# SCH1_Main.net
KiCad netlist of a schematic drawn in Altium Designer
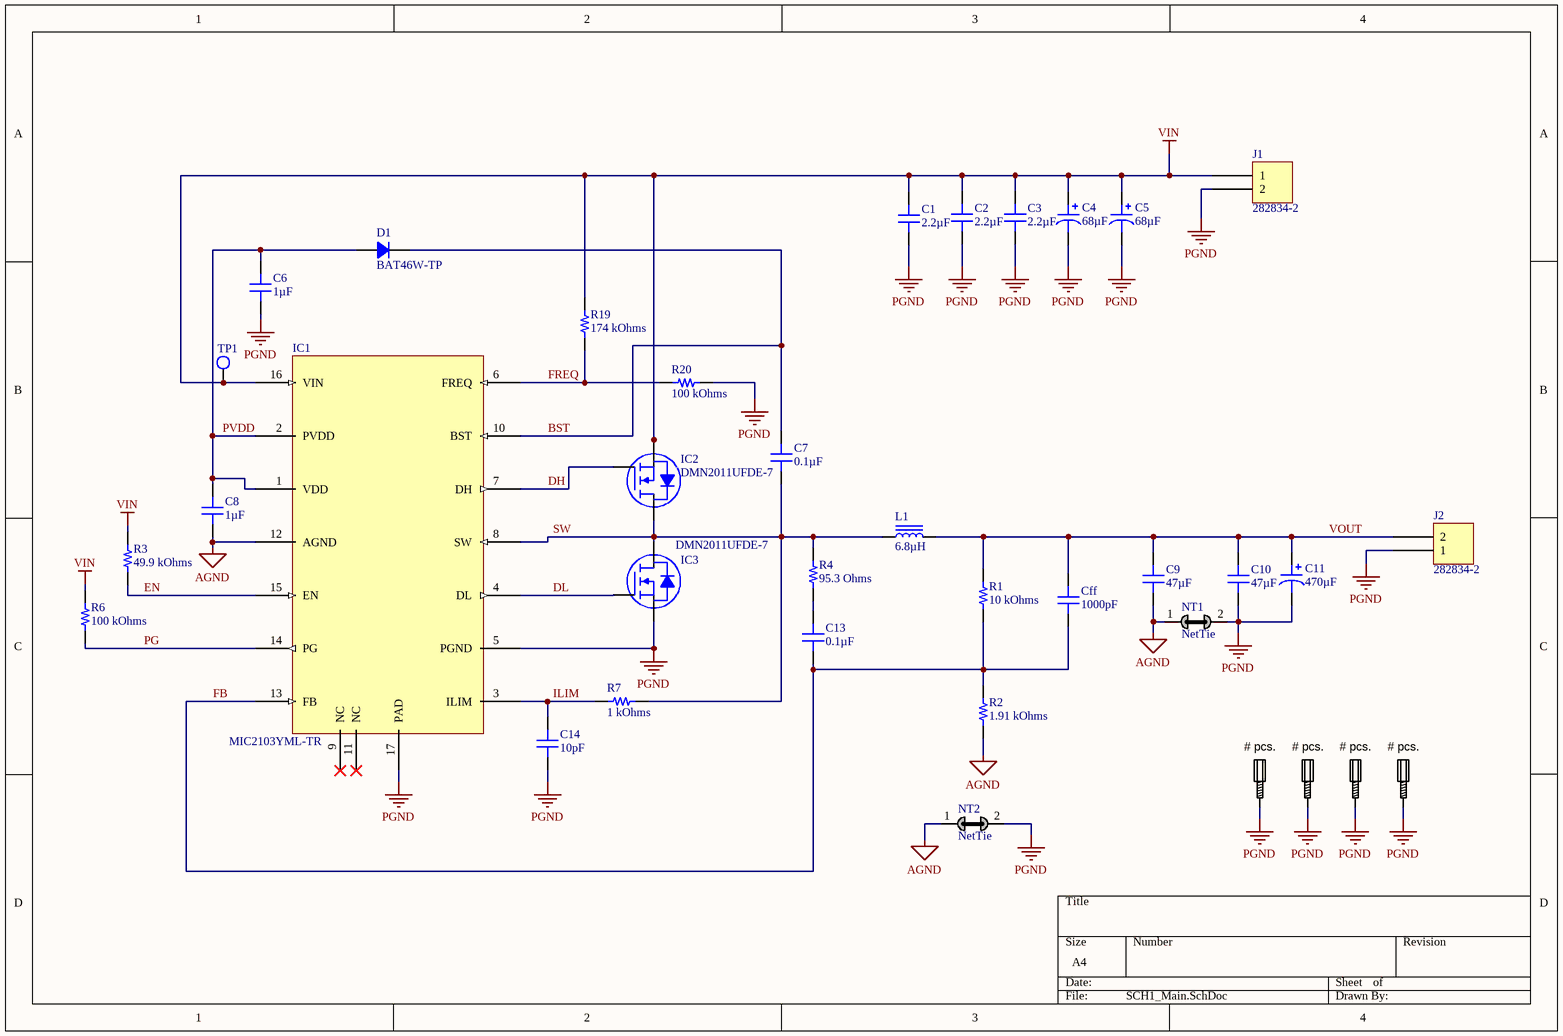
[diagram p0: SCH1_Main.SchDoc]

(export (version "E")
  (design (tool "Eeschema 10.0.6"))
  (components
    (comp (ref "C1")
      (value "2.2µF")
      (footprint "CAP 0805_2012")
      (description "CAP CER 2.2UF 25V X7R 0805")
      (fields (field (name "PART NUMBER") "08053C225K4Z2A") (field (name "MANUFACTURER") "AVX Corporation"))
      (libsource (lib "Celestial Altium Library - altium_library") (part "Capacitor"))
    )
    (comp (ref "C2")
      (value "2.2µF")
      (footprint "CAP 0805_2012")
      (description "CAP CER 2.2UF 25V X7R 0805")
      (fields (field (name "PART NUMBER") "08053C225K4Z2A") (field (name "MANUFACTURER") "AVX Corporation"))
      (libsource (lib "Celestial Altium Library - altium_library") (part "Capacitor"))
    )
    (comp (ref "C3")
      (value "2.2µF")
      (footprint "CAP 0805_2012")
      (description "CAP CER 2.2UF 25V X7R 0805")
      (fields (field (name "PART NUMBER") "08053C225K4Z2A") (field (name "MANUFACTURER") "AVX Corporation"))
      (libsource (lib "Celestial Altium Library - altium_library") (part "Capacitor"))
    )
    (comp (ref "C4")
      (value "68µF")
      (footprint "CAP ALSMD 6.6MM H6.1MM")
      (description "CAP ALUM 68UF 20% 25V SMD")
      (fields (field (name "PART NUMBER") "UWD1E680MCL1GS") (field (name "MANUFACTURER") "Nichicon"))
      (libsource (lib "Celestial Altium Library - altium_library") (part "Polarised Capacitor"))
    )
    (comp (ref "C5")
      (value "68µF")
      (footprint "CAP ALSMD 6.6MM H6.1MM")
      (description "CAP ALUM 68UF 20% 25V SMD")
      (fields (field (name "PART NUMBER") "UWD1E680MCL1GS") (field (name "MANUFACTURER") "Nichicon"))
      (libsource (lib "Celestial Altium Library - altium_library") (part "Polarised Capacitor"))
    )
    (comp (ref "C6")
      (value "1µF")
      (footprint "CAP 0805_2012")
      (description "CAP CER 1UF 25V X5R 0805")
      (fields (field (name "PART NUMBER") "CC0805KKX5R8BB105") (field (name "MANUFACTURER") "Yageo"))
      (libsource (lib "Celestial Altium Library - altium_library") (part "Capacitor"))
    )
    (comp (ref "C7")
      (value "0.1µF")
      (footprint "CAP 0805_2012")
      (description "CAP CER 0.1UF 50V X7R 0805")
      (fields
        (field (name "PART NUMBER") "CL21B104KBFNNNE")
        (field (name "MANUFACTURER") "Samsung Electro-Mechanics")
      )
      (libsource (lib "Celestial Altium Library - altium_library") (part "Capacitor"))
    )
    (comp (ref "C8")
      (value "1µF")
      (footprint "CAP 0805_2012")
      (description "CAP CER 1UF 25V X5R 0805")
      (fields (field (name "PART NUMBER") "CC0805KKX5R8BB105") (field (name "MANUFACTURER") "Yageo"))
      (libsource (lib "Celestial Altium Library - altium_library") (part "Capacitor"))
    )
    (comp (ref "C9")
      (value "47µF")
      (footprint "CAP 1210_3225 - 2.8MM")
      (description "CAP CER 47UF 10V X7T 1210")
      (fields
        (field (name "PART NUMBER") "GRM32ED71A476KE15L")
        (field (name "MANUFACTURER") "Murata Electronics")
      )
      (libsource (lib "Celestial Altium Library - altium_library") (part "Capacitor"))
    )
    (comp (ref "C10")
      (value "47µF")
      (footprint "CAP 1210_3225 - 2.8MM")
      (description "CAP CER 47UF 10V X7T 1210")
      (fields
        (field (name "PART NUMBER") "GRM32ED71A476KE15L")
        (field (name "MANUFACTURER") "Murata Electronics")
      )
      (libsource (lib "Celestial Altium Library - altium_library") (part "Capacitor"))
    )
    (comp (ref "C11")
      (value "470µF")
      (footprint "CAP ALSMD 6.6MM H8.0MM")
      (description "CAP ALUM 470UF 20% 10V SMD")
      (fields
        (field (name "PART NUMBER") "EMZR100ARA471MF80G")
        (field (name "MANUFACTURER") "United Chemi-Con")
      )
      (libsource (lib "Celestial Altium Library - altium_library") (part "Polarised Capacitor"))
    )
    (comp (ref "C13")
      (value "0.1µF")
      (footprint "CAP 0805_2012")
      (description "CAP CER 0.1UF 50V X7R 0805")
      (fields
        (field (name "PART NUMBER") "CL21B104KBFNNNE")
        (field (name "MANUFACTURER") "Samsung Electro-Mechanics")
      )
      (libsource (lib "Celestial Altium Library - altium_library") (part "Capacitor"))
    )
    (comp (ref "C14")
      (value "10pF")
      (footprint "CAP 0805_2012")
      (description "CAP CER 10PF 50V C0G/NP0 0805")
      (fields (field (name "PART NUMBER") "C0805C100J5GACTU") (field (name "MANUFACTURER") "KEMET"))
      (libsource (lib "Celestial Altium Library - altium_library") (part "Capacitor"))
    )
    (comp (ref "Cff")
      (value "1000pF")
      (footprint "CAP 0805_2012")
      (description "CAP CER 1000PF 50V NPO 0805")
      (fields (field (name "PART NUMBER") "CC0805GRNPO9BN102") (field (name "MANUFACTURER") "Yageo"))
      (libsource (lib "Celestial Altium Library - altium_library") (part "Capacitor"))
    )
    (comp (ref "D1")
      (value "BAT46W-TP")
      (footprint "SOD-123")
      (description "DIODE SCHOTTKY 100V 75MA SOD123")
      (fields (field (name "MANUFACTURER") "Micro Commercial Co"))
      (libsource (lib "Celestial Altium Library - altium_library") (part "Diode"))
    )
    (comp (ref "IC1")
      (value "MIC2103YML-TR")
      (footprint "MLF-16_ML_4X4_00")
      (description "IC REG CTRLR BUCK 16MLF")
      (fields
        (field (name "MANUFACTURER") "Microchip")
        (field (name "COPYRIGHT") "Copyright (C) 2018 Accelerated Designs. All rights reserved")
      )
      (libsource (lib "SCH_Lib") (part "MIC2103YML-TR"))
    )
    (comp (ref "IC2")
      (value "DMN2011UFDE-7")
      (footprint "DIODES U-DFN2020-6E")
      (description "MOSFET N-CH 20V 11.7A UDFN2020-6")
      (fields (field (name "MANUFACTURER") "Diodes Incorporated"))
      (libsource (lib "") (part "DIODES INC MOSFET U-DFN2020-6 TYPE E_1"))
    )
    (comp (ref "IC3")
      (value "DMN2011UFDE-7")
      (footprint "DIODES U-DFN2020-6E")
      (description "MOSFET N-CH 20V 11.7A UDFN2020-6")
      (fields (field (name "MANUFACTURER") "Diodes Incorporated"))
      (libsource (lib "Celestial Altium Library - altium_library") (part "DIODES INC MOSFET U-DFN2020-6 TYPE E"))
    )
    (comp (ref "J1")
      (value "282834-2")
      (footprint "TE 282834-2")
      (description "TERM BLK 2P SIDE ENT 2.54MM PCB")
      (fields (field (name "MANUFACTURER") "TE Connectivity AMP Connectors") (field (name "VOLTAGE") "150V"))
      (libsource (lib "") (part "2 Pin_1"))
    )
    (comp (ref "J2")
      (value "282834-2")
      (footprint "TE 282834-2")
      (description "TERM BLK 2P SIDE ENT 2.54MM PCB")
      (fields (field (name "MANUFACTURER") "TE Connectivity AMP Connectors") (field (name "VOLTAGE") "150V"))
      (libsource (lib "Celestial Altium Library - altium_library") (part "2 Pin"))
    )
    (comp (ref "L1")
      (value "6.8µH")
      (footprint "BOURNS SRR1280")
      (description "FIXED IND 6.8UH 7.6A 18.5MOHM SM")
      (fields (field (name "PART NUMBER") "SRR1280-6R8Y") (field (name "MANUFACTURER") "Bourns Inc."))
      (libsource (lib "Celestial Altium Library - altium_library") (part "Inductor"))
    )
    (comp (ref "MECH1")
      (value "# pcs.")
      (footprint "PCB_standoff")
      (description "STANDOFF M/F MET 5MM HEX 10MM L")
      (libsource (lib "SCH_Lib") (part "STANDOFF_M-F_THREADED_M3x8x10mm_HEX_5mm dia"))
    )
    (comp (ref "MECH2")
      (value "# pcs.")
      (footprint "PCB_standoff")
      (description "STANDOFF M/F MET 5MM HEX 10MM L")
      (libsource (lib "SCH_Lib") (part "STANDOFF_M-F_THREADED_M3x8x10mm_HEX_5mm dia"))
    )
    (comp (ref "MECH3")
      (value "# pcs.")
      (footprint "PCB_standoff")
      (description "STANDOFF M/F MET 5MM HEX 10MM L")
      (libsource (lib "SCH_Lib") (part "STANDOFF_M-F_THREADED_M3x8x10mm_HEX_5mm dia"))
    )
    (comp (ref "MECH4")
      (value "# pcs.")
      (footprint "PCB_standoff")
      (description "STANDOFF M/F MET 5MM HEX 10MM L")
      (libsource (lib "SCH_Lib") (part "STANDOFF_M-F_THREADED_M3x8x10mm_HEX_5mm dia"))
    )
    (comp (ref "NT1")
      (value "NetTie")
      (footprint "NetTie_Narrow2")
      (libsource (lib "SCH_Lib") (part "NetTie"))
    )
    (comp (ref "NT2")
      (value "NetTie")
      (footprint "NetTie_Narrow2")
      (libsource (lib "SCH_Lib") (part "NetTie"))
    )
    (comp (ref "R1")
      (value "10 kOhms")
      (footprint "RES 0805_2012")
      (description "RES SMD 10K OHM 1% 1/4W 0805")
      (fields (field (name "PART NUMBER") "CRS0805-FX-1002ELF") (field (name "MANUFACTURER") "Bourns Inc."))
      (libsource (lib "Celestial Altium Library - altium_library") (part "Resistor"))
    )
    (comp (ref "R2")
      (value "1.91 kOhms")
      (footprint "RES 0805_2012")
      (description "RES SMD 1.91K OHM 0.1% 1/8W 0805")
      (fields (field (name "PART NUMBER") "RT0805BRD071K91L") (field (name "MANUFACTURER") "Yageo"))
      (libsource (lib "Celestial Altium Library - altium_library") (part "Resistor"))
    )
    (comp (ref "R3")
      (value "49.9 kOhms")
      (footprint "RES 0805_2012")
      (description "RES SMD 49.9K OHM 1% 1/8W 0805")
      (fields (field (name "PART NUMBER") "CRCW080549K9FKEAC") (field (name "MANUFACTURER") "Vishay Dale"))
      (libsource (lib "Celestial Altium Library - altium_library") (part "Resistor"))
    )
    (comp (ref "R4")
      (value "95.3 Ohms")
      (footprint "RES 0805_2012")
      (description "RES 95.3 OHM 0.1% 1/8W 0805")
      (fields
        (field (name "PART NUMBER") "ERA-6AEB95R3V")
        (field (name "MANUFACTURER") "Panasonic Electronic Components")
      )
      (libsource (lib "Celestial Altium Library - altium_library") (part "Resistor"))
    )
    (comp (ref "R6")
      (value "100 kOhms")
      (footprint "RES 0805_2012")
      (description "RES SMD 100K OHM 5% 1/8W 0805")
      (fields
        (field (name "PART NUMBER") "ERJ-6GEYJ104V")
        (field (name "MANUFACTURER") "Panasonic Electronic Components")
      )
      (libsource (lib "Celestial Altium Library - altium_library") (part "Resistor"))
    )
    (comp (ref "R7")
      (value "1 kOhms")
      (footprint "RES 0805_2012")
      (description "RES SMD 1K OHM 0.5% 1/8W 0805")
      (fields (field (name "PART NUMBER") "RT0805DRD071KL") (field (name "MANUFACTURER") "Yageo"))
      (libsource (lib "Celestial Altium Library - altium_library") (part "Resistor"))
    )
    (comp (ref "R19")
      (value "174 kOhms")
      (footprint "RES 0805_2012")
      (description "RES SMD 174K OHM 1% 1/8W 0805")
      (fields
        (field (name "PART NUMBER") "ERJ-6ENF1743V")
        (field (name "MANUFACTURER") "Panasonic Electronic Components")
      )
      (libsource (lib "Celestial Altium Library - altium_library") (part "Resistor"))
    )
    (comp (ref "R20")
      (value "100 kOhms")
      (footprint "RES 0805_2012")
      (description "RES SMD 100K OHM 5% 1/8W 0805")
      (fields
        (field (name "PART NUMBER") "ERJ-6GEYJ104V")
        (field (name "MANUFACTURER") "Panasonic Electronic Components")
      )
      (libsource (lib "Celestial Altium Library - altium_library") (part "Resistor"))
    )
    (comp (ref "TP1")
      (value "Test Point")
      (footprint "TestPoint-1.5mm")
      (libsource (lib "SCH_Lib") (part "Test Point"))
    )
  )
  (nets
    (net (code "1") (name "/BST") (class "Default")
      (node (ref "C7") (pin "2") (pinfunction "2_2") (pintype "passive"))
      (node (ref "D1") (pin "2") (pinfunction "2_2") (pintype "passive"))
      (node (ref "IC1") (pin "10") (pinfunction "BST_10") (pintype "input"))
    )
    (net (code "2") (name "/DH") (class "Default")
      (node (ref "IC1") (pin "7") (pinfunction "DH_7") (pintype "output"))
      (node (ref "IC2") (pin "G") (pinfunction "G_G") (pintype "passive"))
    )
    (net (code "3") (name "/DL") (class "Default")
      (node (ref "IC1") (pin "4") (pinfunction "DL_4") (pintype "output"))
      (node (ref "IC3") (pin "G") (pinfunction "G_G") (pintype "passive"))
    )
    (net (code "4") (name "/EN") (class "Default")
      (node (ref "IC1") (pin "15") (pinfunction "EN_15") (pintype "input"))
      (node (ref "R3") (pin "1") (pinfunction "1_1") (pintype "passive"))
    )
    (net (code "5") (name "/FB") (class "Default")
      (node (ref "C13") (pin "1") (pinfunction "1_1") (pintype "passive"))
      (node (ref "Cff") (pin "1") (pinfunction "1_1") (pintype "passive"))
      (node (ref "IC1") (pin "13") (pinfunction "FB_13") (pintype "input"))
      (node (ref "R1") (pin "1") (pinfunction "1_1") (pintype "passive"))
      (node (ref "R2") (pin "2") (pinfunction "2_2") (pintype "passive"))
    )
    (net (code "6") (name "/FREQ") (class "Default")
      (node (ref "IC1") (pin "6") (pinfunction "FREQ_6") (pintype "input"))
      (node (ref "R19") (pin "1") (pinfunction "1_1") (pintype "passive"))
      (node (ref "R20") (pin "2") (pinfunction "2_2") (pintype "passive"))
    )
    (net (code "7") (name "/ILIM") (class "Default")
      (node (ref "C14") (pin "2") (pinfunction "2_2") (pintype "passive"))
      (node (ref "IC1") (pin "3") (pinfunction "ILIM_3") (pintype "passive"))
      (node (ref "R7") (pin "1") (pinfunction "1_1") (pintype "passive"))
    )
    (net (code "8") (name "/PG") (class "Default")
      (node (ref "IC1") (pin "14") (pinfunction "PG_14") (pintype "output"))
      (node (ref "R6") (pin "1") (pinfunction "1_1") (pintype "passive"))
    )
    (net (code "9") (name "/PVDD") (class "Default")
      (node (ref "C6") (pin "2") (pinfunction "2_2") (pintype "passive"))
      (node (ref "C8") (pin "2") (pinfunction "2_2") (pintype "passive"))
      (node (ref "D1") (pin "1") (pinfunction "1_1") (pintype "passive"))
      (node (ref "IC1") (pin "1") (pinfunction "VDD_1") (pintype "power_in"))
      (node (ref "IC1") (pin "2") (pinfunction "PVDD_2") (pintype "power_in"))
    )
    (net (code "10") (name "/SW") (class "Default")
      (node (ref "C7") (pin "1") (pinfunction "1_1") (pintype "passive"))
      (node (ref "IC1") (pin "8") (pinfunction "SW_8") (pintype "input"))
      (node (ref "IC2") (pin "D") (pinfunction "Drain_D") (pintype "passive"))
      (node (ref "IC3") (pin "D") (pinfunction "Drain_D") (pintype "passive"))
      (node (ref "L1") (pin "1") (pinfunction "1_1") (pintype "passive"))
      (node (ref "R4") (pin "2") (pinfunction "2_2") (pintype "passive"))
      (node (ref "R7") (pin "2") (pinfunction "2_2") (pintype "passive"))
    )
    (net (code "11") (name "/VOUT") (class "Default")
      (node (ref "C10") (pin "2") (pinfunction "2_2") (pintype "passive"))
      (node (ref "C11") (pin "1") (pinfunction "1_1") (pintype "passive"))
      (node (ref "C9") (pin "2") (pinfunction "2_2") (pintype "passive"))
      (node (ref "Cff") (pin "2") (pinfunction "2_2") (pintype "passive"))
      (node (ref "J2") (pin "2") (pinfunction "2_2") (pintype "passive"))
      (node (ref "L1") (pin "2") (pinfunction "2_2") (pintype "passive"))
      (node (ref "R1") (pin "2") (pinfunction "2_2") (pintype "passive"))
    )
    (net (code "12") (name "AGND") (class "Default")
      (node (ref "C8") (pin "1") (pinfunction "1_1") (pintype "passive"))
      (node (ref "C9") (pin "1") (pinfunction "1_1") (pintype "passive"))
      (node (ref "IC1") (pin "12") (pinfunction "AGND_12") (pintype "power_in"))
      (node (ref "NT1") (pin "1") (pinfunction "1_1") (pintype "passive"))
      (node (ref "NT2") (pin "1") (pinfunction "1_1") (pintype "passive"))
      (node (ref "R2") (pin "1") (pinfunction "1_1") (pintype "passive"))
    )
    (net (code "13") (name "Net-(C13-Pad2)") (class "Default")
      (node (ref "C13") (pin "2") (pinfunction "2_2") (pintype "passive"))
      (node (ref "R4") (pin "1") (pinfunction "1_1") (pintype "passive"))
    )
    (net (code "14") (name "PGND") (class "Default")
      (node (ref "C1") (pin "1") (pinfunction "1_1") (pintype "passive"))
      (node (ref "C10") (pin "1") (pinfunction "1_1") (pintype "passive"))
      (node (ref "C11") (pin "2") (pinfunction "2_2") (pintype "passive"))
      (node (ref "C14") (pin "1") (pinfunction "1_1") (pintype "passive"))
      (node (ref "C2") (pin "1") (pinfunction "1_1") (pintype "passive"))
      (node (ref "C3") (pin "1") (pinfunction "1_1") (pintype "passive"))
      (node (ref "C4") (pin "2") (pinfunction "2_2") (pintype "passive"))
      (node (ref "C5") (pin "2") (pinfunction "2_2") (pintype "passive"))
      (node (ref "C6") (pin "1") (pinfunction "1_1") (pintype "passive"))
      (node (ref "IC1") (pin "17") (pinfunction "PAD_17") (pintype "passive"))
      (node (ref "IC1") (pin "5") (pinfunction "PGND_5") (pintype "power_in"))
      (node (ref "IC3") (pin "S") (pinfunction "S_S") (pintype "passive"))
      (node (ref "J1") (pin "2") (pinfunction "2_2") (pintype "passive"))
      (node (ref "J2") (pin "1") (pinfunction "1_1") (pintype "passive"))
      (node (ref "MECH1") (pin "MH1") (pinfunction "MH1_MH1") (pintype "passive"))
      (node (ref "MECH2") (pin "MH1") (pinfunction "MH1_MH1") (pintype "passive"))
      (node (ref "MECH3") (pin "MH1") (pinfunction "MH1_MH1") (pintype "passive"))
      (node (ref "MECH4") (pin "MH1") (pinfunction "MH1_MH1") (pintype "passive"))
      (node (ref "NT1") (pin "2") (pinfunction "2_2") (pintype "passive"))
      (node (ref "NT2") (pin "2") (pinfunction "2_2") (pintype "passive"))
      (node (ref "R20") (pin "1") (pinfunction "1_1") (pintype "passive"))
    )
    (net (code "15") (name "VIN") (class "Default")
      (node (ref "C1") (pin "2") (pinfunction "2_2") (pintype "passive"))
      (node (ref "C2") (pin "2") (pinfunction "2_2") (pintype "passive"))
      (node (ref "C3") (pin "2") (pinfunction "2_2") (pintype "passive"))
      (node (ref "C4") (pin "1") (pinfunction "1_1") (pintype "passive"))
      (node (ref "C5") (pin "1") (pinfunction "1_1") (pintype "passive"))
      (node (ref "IC1") (pin "16") (pinfunction "VIN_16") (pintype "input"))
      (node (ref "IC2") (pin "S") (pinfunction "S_S") (pintype "passive"))
      (node (ref "J1") (pin "1") (pinfunction "1_1") (pintype "passive"))
      (node (ref "R19") (pin "2") (pinfunction "2_2") (pintype "passive"))
      (node (ref "R3") (pin "2") (pinfunction "2_2") (pintype "passive"))
      (node (ref "R6") (pin "2") (pinfunction "2_2") (pintype "passive"))
      (node (ref "TP1") (pin "1") (pinfunction "TP_1") (pintype "passive"))
    )
    (net (code "16") (name "unconnected-(IC1-NC-Pad9)") (class "Default")
      (node (ref "IC1") (pin "9") (pinfunction "NC_9") (pintype "passive+no_connect"))
    )
    (net (code "17") (name "unconnected-(IC1-NC-Pad11)") (class "Default")
      (node (ref "IC1") (pin "11") (pinfunction "NC_11") (pintype "passive+no_connect"))
    )
  )
)
